# connect.net
KiCad netlist of a schematic drawn in Altium Designer
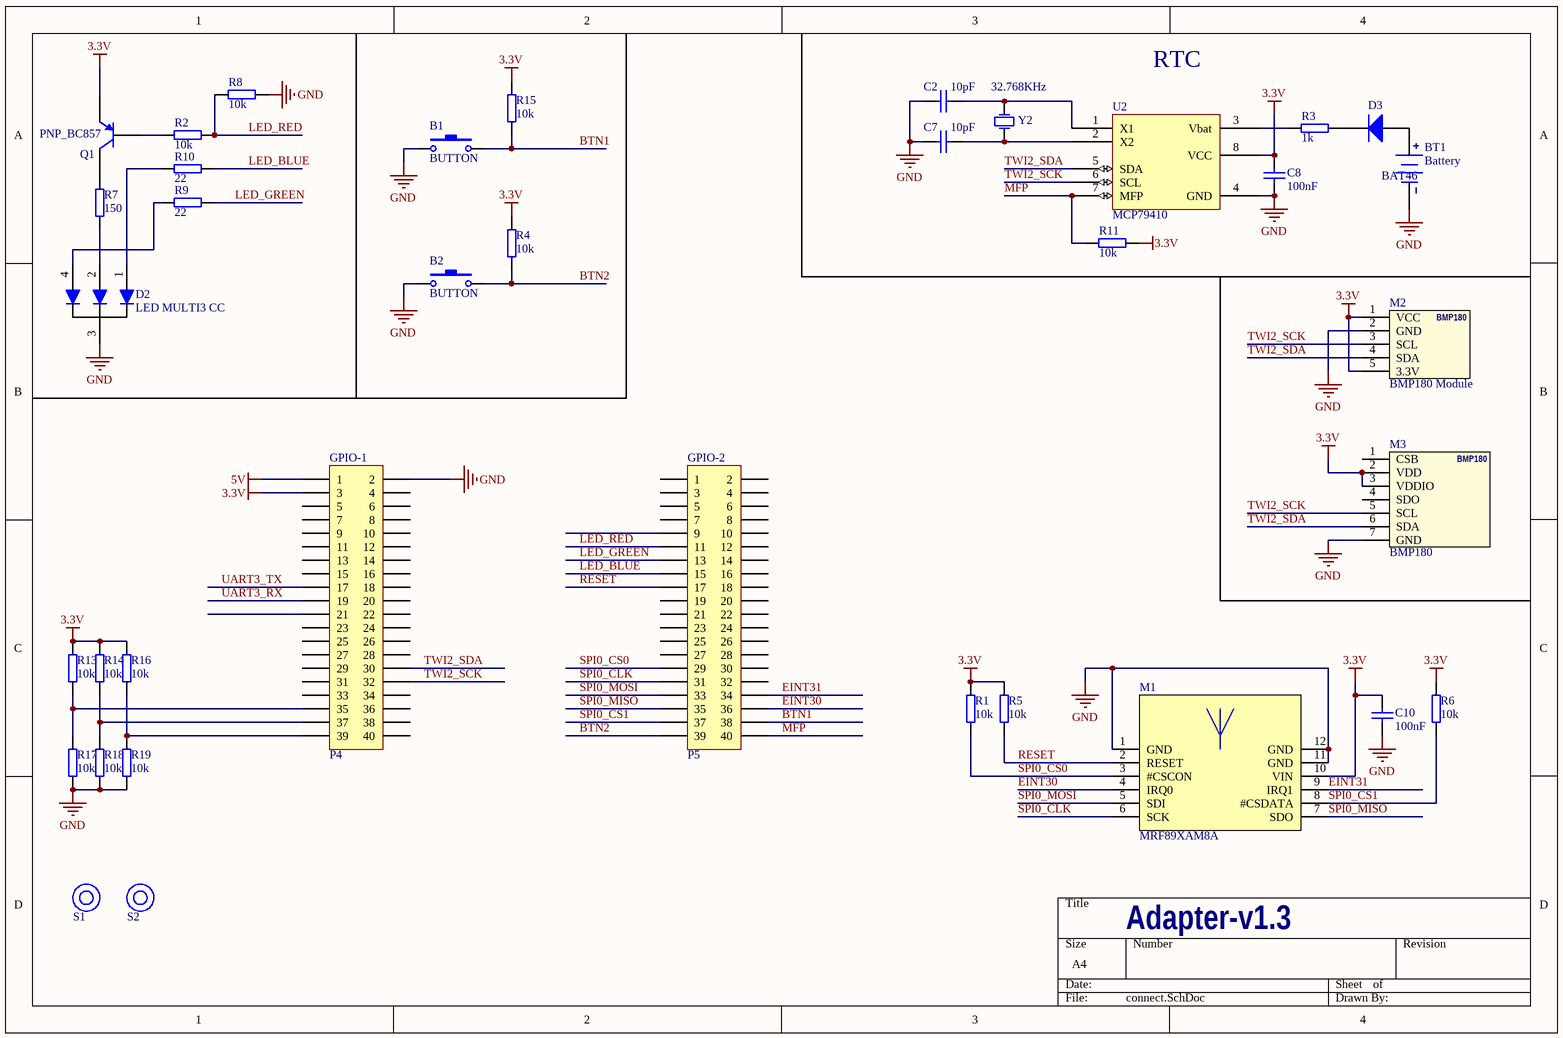
[diagram p0: connect.SchDoc]

(export (version "E")
  (design (tool "Eeschema 10.0.6"))
  (components
    (comp (ref "B1")
      (value "BUTTON")
      (footprint "SPST_BTN")
      (description "Switch Button KSS341G")
      (fields (field (name "PUBLISHER") "Altium Limited"))
      (libsource (lib "ANY Devices") (part "SW-PB_1"))
    )
    (comp (ref "B2")
      (value "BUTTON")
      (footprint "SPST_BTN")
      (description "Switch Button KSS341G")
      (fields (field (name "PUBLISHER") "Altium Limited"))
      (libsource (lib "ANY Devices") (part "SW-PB_1"))
    )
    (comp (ref "BT1")
      (value "Battery")
      (footprint "BATT1220-horizontal")
      (description "Multicell Battery")
      (fields (field (name "PUBLISHER") "Altium Limited"))
      (libsource (lib "ANY Devices") (part "Battery"))
    )
    (comp (ref "C2")
      (value "10pF")
      (footprint "C0805")
      (description "Capacitor")
      (fields (field (name "PUBLISHER") "Altium Limited"))
      (libsource (lib "ANY Devices") (part "Cap"))
    )
    (comp (ref "C7")
      (value "10pF")
      (footprint "C0805")
      (description "Capacitor")
      (fields (field (name "PUBLISHER") "Altium Limited"))
      (libsource (lib "ANY Devices") (part "Cap"))
    )
    (comp (ref "C8")
      (value "100nF")
      (footprint "C0805")
      (description "Capacitor")
      (fields (field (name "PUBLISHER") "Altium Limited"))
      (libsource (lib "ANY Devices") (part "Cap"))
    )
    (comp (ref "C10")
      (value "100nF")
      (footprint "C0805")
      (description "Capacitor")
      (fields (field (name "PUBLISHER") "Altium Limited"))
      (libsource (lib "ANY Devices") (part "Cap"))
    )
    (comp (ref "D2")
      (value "LED MULTI3 CC")
      (footprint "LED_MULTI - AXIAL")
      (description "COMMON CATHODE, HSMF-A211-A00J1 - LED, SMD, RED/YEL-GRN")
      (libsource (lib "ANY Devices") (part "LED MULTI3 CC"))
    )
    (comp (ref "D3")
      (value "BAT46")
      (footprint "SOD-323")
      (description "Default Diode")
      (fields (field (name "PUBLISHER") "Altium Limited"))
      (libsource (lib "ANY Devices") (part "Diode"))
    )
    (comp (ref "M1")
      (value "MRF89XAM8A")
      (footprint "MRF89XAM8A")
      (description "868 MHz Ultra-Low Power  Sub-GHz Transceiver Module")
      (libsource (lib "Modules") (part "MRF89XAM8A"))
    )
    (comp (ref "M2")
      (value "BMP180 Module")
      (footprint "BMP180_MODULE")
      (description "Digital Barometric Pressure Sensor Module")
      (libsource (lib "Modules") (part "BMP180_MODULE"))
    )
    (comp (ref "M3")
      (value "BMP180")
      (footprint "BMP180")
      (description "Digital pressure sensor")
      (libsource (lib "ANY Devices") (part "BMP180"))
    )
    (comp (ref "P4")
      (value "GPIO-1")
      (footprint "HDR127-20-F")
      (description "Header, 40-Pin, pitch 1.27mm")
      (fields (field (name "PUBLISHER") "Altium Limited"))
      (libsource (lib "ANY Connectors") (part "HDR127 20X2"))
    )
    (comp (ref "P5")
      (value "GPIO-2")
      (footprint "HDR127-20-F")
      (description "Header, 40-Pin, pitch 1.27mm")
      (fields (field (name "PUBLISHER") "Altium Limited"))
      (libsource (lib "ANY Connectors") (part "HDR127 20X2"))
    )
    (comp (ref "Q1")
      (value "PNP_BC857")
      (footprint "SOT23")
      (description "PNP Bipolar Transistor")
      (fields (field (name "PUBLISHER") "Altium Limited"))
      (libsource (lib "ANY Devices") (part "PNP_BC857"))
    )
    (comp (ref "R1")
      (value "10k")
      (footprint "R0805")
      (description "Resistor")
      (fields (field (name "PUBLISHER") "Altium Limited"))
      (libsource (lib "") (part "Res2_2"))
    )
    (comp (ref "R2")
      (value "10k")
      (footprint "R0805")
      (description "Resistor")
      (fields (field (name "PUBLISHER") "Altium Limited"))
      (libsource (lib "") (part "Res2_1"))
    )
    (comp (ref "R3")
      (value "1k")
      (footprint "R0805")
      (description "Resistor")
      (fields (field (name "PUBLISHER") "Altium Limited"))
      (libsource (lib "") (part "Res2_3"))
    )
    (comp (ref "R4")
      (value "10k")
      (footprint "R0805")
      (description "Resistor")
      (fields (field (name "PUBLISHER") "Altium Limited"))
      (libsource (lib "") (part "Res2_2"))
    )
    (comp (ref "R5")
      (value "10k")
      (footprint "R0805")
      (description "Resistor")
      (fields (field (name "PUBLISHER") "Altium Limited"))
      (libsource (lib "") (part "Res2_2"))
    )
    (comp (ref "R6")
      (value "10k")
      (footprint "R0805")
      (description "Resistor")
      (fields (field (name "PUBLISHER") "Altium Limited"))
      (libsource (lib "") (part "Res2_2"))
    )
    (comp (ref "R7")
      (value "150")
      (footprint "R0805")
      (description "Resistor")
      (fields (field (name "PUBLISHER") "Altium Limited"))
      (libsource (lib "ANY Devices") (part "Res2"))
    )
    (comp (ref "R8")
      (value "10k")
      (footprint "R0805")
      (description "Resistor")
      (fields (field (name "PUBLISHER") "Altium Limited"))
      (libsource (lib "") (part "Res2_1"))
    )
    (comp (ref "R9")
      (value "22")
      (footprint "R0805")
      (description "Resistor")
      (fields (field (name "PUBLISHER") "Altium Limited"))
      (libsource (lib "") (part "Res2_1"))
    )
    (comp (ref "R10")
      (value "22")
      (footprint "R0805")
      (description "Resistor")
      (fields (field (name "PUBLISHER") "Altium Limited"))
      (libsource (lib "") (part "Res2_3"))
    )
    (comp (ref "R11")
      (value "10k")
      (footprint "R0805")
      (description "Resistor")
      (fields (field (name "PUBLISHER") "Altium Limited"))
      (libsource (lib "") (part "Res2_1"))
    )
    (comp (ref "R13")
      (value "10k")
      (footprint "R0805")
      (description "Resistor")
      (fields (field (name "PUBLISHER") "Altium Limited"))
      (libsource (lib "ANY Devices") (part "Res2"))
    )
    (comp (ref "R14")
      (value "10k")
      (footprint "R0805")
      (description "Resistor")
      (fields (field (name "PUBLISHER") "Altium Limited"))
      (libsource (lib "ANY Devices") (part "Res2"))
    )
    (comp (ref "R15")
      (value "10k")
      (footprint "R0805")
      (description "Resistor")
      (fields (field (name "PUBLISHER") "Altium Limited"))
      (libsource (lib "") (part "Res2_2"))
    )
    (comp (ref "R16")
      (value "10k")
      (footprint "R0805")
      (description "Resistor")
      (fields (field (name "PUBLISHER") "Altium Limited"))
      (libsource (lib "ANY Devices") (part "Res2"))
    )
    (comp (ref "R17")
      (value "10k")
      (footprint "R0805")
      (description "Resistor")
      (fields (field (name "PUBLISHER") "Altium Limited"))
      (libsource (lib "ANY Devices") (part "Res2"))
    )
    (comp (ref "R18")
      (value "10k")
      (footprint "R0805")
      (description "Resistor")
      (fields (field (name "PUBLISHER") "Altium Limited"))
      (libsource (lib "ANY Devices") (part "Res2"))
    )
    (comp (ref "R19")
      (value "10k")
      (footprint "R0805")
      (description "Resistor")
      (fields (field (name "PUBLISHER") "Altium Limited"))
      (libsource (lib "ANY Devices") (part "Res2"))
    )
    (comp (ref "S1") (value "TARGET") (footprint "TARGET") (libsource (lib "ANY Devices") (part "TARGET")))
    (comp (ref "S2") (value "TARGET") (footprint "TARGET") (libsource (lib "ANY Devices") (part "TARGET")))
    (comp (ref "U2")
      (value "MCP79410")
      (footprint "SO8_M")
      (description "Microchip i2c RTC real time clock")
      (libsource (lib "ANYlib") (part "MCP79410"))
    )
    (comp (ref "Y2")
      (value "32.768KHz")
      (footprint "R38")
      (description "Crystal Oscillator")
      (fields (field (name "PUBLISHER") "Altium Limited"))
      (libsource (lib "ANY Devices") (part "XTAL"))
    )
  )
  (nets
    (net (code "1") (name "/BTN1") (class "Default")
      (node (ref "B1") (pin "2") (pinfunction "2_2") (pintype "passive"))
      (node (ref "P5") (pin "38") (pinfunction "38_38") (pintype "passive"))
      (node (ref "R15") (pin "1") (pinfunction "1_1") (pintype "passive"))
    )
    (net (code "2") (name "/BTN2") (class "Default")
      (node (ref "B2") (pin "2") (pinfunction "2_2") (pintype "passive"))
      (node (ref "P5") (pin "39") (pinfunction "39_39") (pintype "passive"))
      (node (ref "R4") (pin "1") (pinfunction "1_1") (pintype "passive"))
    )
    (net (code "3") (name "/EINT30") (class "Default")
      (node (ref "M1") (pin "4") (pinfunction "IRQ0_4") (pintype "passive"))
      (node (ref "P5") (pin "36") (pinfunction "36_36") (pintype "passive"))
    )
    (net (code "4") (name "/EINT31") (class "Default")
      (node (ref "M1") (pin "9") (pinfunction "IRQ1_9") (pintype "passive"))
      (node (ref "P5") (pin "34") (pinfunction "34_34") (pintype "passive"))
    )
    (net (code "5") (name "/LED_BLUE") (class "Default")
      (node (ref "P5") (pin "15") (pinfunction "15_15") (pintype "passive"))
      (node (ref "R10") (pin "2") (pinfunction "2_2") (pintype "passive"))
    )
    (net (code "6") (name "/LED_GREEN") (class "Default")
      (node (ref "P5") (pin "13") (pinfunction "13_13") (pintype "passive"))
      (node (ref "R9") (pin "1") (pinfunction "1_1") (pintype "passive"))
    )
    (net (code "7") (name "/LED_RED") (class "Default")
      (node (ref "P5") (pin "11") (pinfunction "11_11") (pintype "passive"))
      (node (ref "R2") (pin "1") (pinfunction "1_1") (pintype "passive"))
      (node (ref "R8") (pin "2") (pinfunction "2_2") (pintype "passive"))
    )
    (net (code "8") (name "/MFP") (class "Default")
      (node (ref "P5") (pin "40") (pinfunction "40_40") (pintype "passive"))
      (node (ref "R11") (pin "2") (pinfunction "2_2") (pintype "passive"))
      (node (ref "U2") (pin "7") (pinfunction "MFP_7") (pintype "bidirectional"))
    )
    (net (code "9") (name "/RESET") (class "Default")
      (node (ref "M1") (pin "2") (pinfunction "RESET_2") (pintype "passive"))
      (node (ref "P5") (pin "17") (pinfunction "17_17") (pintype "passive"))
      (node (ref "R5") (pin "1") (pinfunction "1_1") (pintype "passive"))
    )
    (net (code "10") (name "/SPI0_CLK") (class "Default")
      (node (ref "M1") (pin "6") (pinfunction "SCK_6") (pintype "passive"))
      (node (ref "P5") (pin "31") (pinfunction "31_31") (pintype "passive"))
    )
    (net (code "11") (name "/SPI0_CS0") (class "Default")
      (node (ref "M1") (pin "3") (pinfunction "#CSCON_3") (pintype "passive"))
      (node (ref "P5") (pin "29") (pinfunction "29_29") (pintype "passive"))
      (node (ref "R1") (pin "1") (pinfunction "1_1") (pintype "passive"))
    )
    (net (code "12") (name "/SPI0_CS1") (class "Default")
      (node (ref "M1") (pin "8") (pinfunction "#CSDATA_8") (pintype "passive"))
      (node (ref "P5") (pin "37") (pinfunction "37_37") (pintype "passive"))
      (node (ref "R6") (pin "1") (pinfunction "1_1") (pintype "passive"))
    )
    (net (code "13") (name "/SPI0_MISO") (class "Default")
      (node (ref "M1") (pin "7") (pinfunction "SDO_7") (pintype "passive"))
      (node (ref "P5") (pin "35") (pinfunction "35_35") (pintype "passive"))
    )
    (net (code "14") (name "/SPI0_MOSI") (class "Default")
      (node (ref "M1") (pin "5") (pinfunction "SDI_5") (pintype "passive"))
      (node (ref "P5") (pin "33") (pinfunction "33_33") (pintype "passive"))
    )
    (net (code "15") (name "/TWI2_SCK") (class "Default")
      (node (ref "M2") (pin "3") (pinfunction "SCL_3") (pintype "passive"))
      (node (ref "M3") (pin "5") (pinfunction "SCL_5") (pintype "passive"))
      (node (ref "P4") (pin "32") (pinfunction "32_32") (pintype "passive"))
      (node (ref "U2") (pin "6") (pinfunction "SCL_6") (pintype "bidirectional"))
    )
    (net (code "16") (name "/TWI2_SDA") (class "Default")
      (node (ref "M2") (pin "4") (pinfunction "SDA_4") (pintype "passive"))
      (node (ref "M3") (pin "6") (pinfunction "SDA_6") (pintype "passive"))
      (node (ref "P4") (pin "30") (pinfunction "30_30") (pintype "passive"))
      (node (ref "U2") (pin "5") (pinfunction "SDA_5") (pintype "bidirectional"))
    )
    (net (code "17") (name "/UART3_RX") (class "Default")
      (node (ref "P4") (pin "19") (pinfunction "19_19") (pintype "passive"))
    )
    (net (code "18") (name "/UART3_TX") (class "Default")
      (node (ref "P4") (pin "17") (pinfunction "17_17") (pintype "passive"))
    )
    (net (code "19") (name "3.3V") (class "Default")
      (node (ref "C10") (pin "2") (pinfunction "2_2") (pintype "passive"))
      (node (ref "C8") (pin "2") (pinfunction "2_2") (pintype "passive"))
      (node (ref "M1") (pin "10") (pinfunction "VIN_10") (pintype "passive"))
      (node (ref "M2") (pin "1") (pinfunction "VCC_1") (pintype "passive"))
      (node (ref "M2") (pin "5") (pinfunction "3.3V_5") (pintype "passive"))
      (node (ref "M3") (pin "2") (pinfunction "VDD_2") (pintype "passive"))
      (node (ref "M3") (pin "3") (pinfunction "VDDIO_3") (pintype "passive"))
      (node (ref "P4") (pin "3") (pinfunction "3_3") (pintype "passive"))
      (node (ref "Q1") (pin "2") (pinfunction "E_2") (pintype "passive"))
      (node (ref "R1") (pin "2") (pinfunction "2_2") (pintype "passive"))
      (node (ref "R11") (pin "1") (pinfunction "1_1") (pintype "passive"))
      (node (ref "R13") (pin "1") (pinfunction "1_1") (pintype "passive"))
      (node (ref "R14") (pin "1") (pinfunction "1_1") (pintype "passive"))
      (node (ref "R15") (pin "2") (pinfunction "2_2") (pintype "passive"))
      (node (ref "R16") (pin "1") (pinfunction "1_1") (pintype "passive"))
      (node (ref "R4") (pin "2") (pinfunction "2_2") (pintype "passive"))
      (node (ref "R5") (pin "2") (pinfunction "2_2") (pintype "passive"))
      (node (ref "R6") (pin "2") (pinfunction "2_2") (pintype "passive"))
      (node (ref "U2") (pin "8") (pinfunction "VCC_8") (pintype "power_in"))
    )
    (net (code "20") (name "5V") (class "Default")
      (node (ref "P4") (pin "1") (pinfunction "1_1") (pintype "passive"))
    )
    (net (code "21") (name "GND") (class "Default")
      (node (ref "B1") (pin "1") (pinfunction "1_1") (pintype "passive"))
      (node (ref "B2") (pin "1") (pinfunction "1_1") (pintype "passive"))
      (node (ref "BT1") (pin "2") (pinfunction "-_2") (pintype "passive"))
      (node (ref "C10") (pin "1") (pinfunction "1_1") (pintype "passive"))
      (node (ref "C2") (pin "1") (pinfunction "1_1") (pintype "passive"))
      (node (ref "C7") (pin "1") (pinfunction "1_1") (pintype "passive"))
      (node (ref "C8") (pin "1") (pinfunction "1_1") (pintype "passive"))
      (node (ref "D2") (pin "3") (pinfunction "C_3") (pintype "passive"))
      (node (ref "M1") (pin "1") (pinfunction "GND_1") (pintype "passive"))
      (node (ref "M1") (pin "11") (pinfunction "GND_11") (pintype "passive"))
      (node (ref "M1") (pin "12") (pinfunction "GND_12") (pintype "passive"))
      (node (ref "M2") (pin "2") (pinfunction "GND_2") (pintype "passive"))
      (node (ref "M3") (pin "7") (pinfunction "GND_7") (pintype "passive"))
      (node (ref "P4") (pin "2") (pinfunction "2_2") (pintype "passive"))
      (node (ref "R17") (pin "2") (pinfunction "2_2") (pintype "passive"))
      (node (ref "R18") (pin "2") (pinfunction "2_2") (pintype "passive"))
      (node (ref "R19") (pin "2") (pinfunction "2_2") (pintype "passive"))
      (node (ref "R8") (pin "1") (pinfunction "1_1") (pintype "passive"))
      (node (ref "U2") (pin "4") (pinfunction "GND_4") (pintype "power_in"))
    )
    (net (code "22") (name "Net-(BT1-+)") (class "Default")
      (node (ref "BT1") (pin "1") (pinfunction "+_1") (pintype "passive"))
      (node (ref "D3") (pin "1") (pinfunction "A_1") (pintype "passive"))
    )
    (net (code "23") (name "Net-(D2-A)") (class "Default")
      (node (ref "D2") (pin "2") (pinfunction "A_2") (pintype "passive"))
      (node (ref "R7") (pin "2") (pinfunction "2_2") (pintype "passive"))
    )
    (net (code "24") (name "Net-(D2-C-Pad1)") (class "Default")
      (node (ref "D2") (pin "1") (pinfunction "C_1") (pintype "passive"))
      (node (ref "R10") (pin "1") (pinfunction "1_1") (pintype "passive"))
    )
    (net (code "25") (name "Net-(D2-C-Pad4)") (class "Default")
      (node (ref "D2") (pin "4") (pinfunction "C_4") (pintype "passive"))
      (node (ref "R9") (pin "2") (pinfunction "2_2") (pintype "passive"))
    )
    (net (code "26") (name "Net-(D3-K)") (class "Default")
      (node (ref "D3") (pin "2") (pinfunction "K_2") (pintype "passive"))
      (node (ref "R3") (pin "2") (pinfunction "2_2") (pintype "passive"))
    )
    (net (code "27") (name "Net-(P4-Pad35)") (class "Default")
      (node (ref "P4") (pin "35") (pinfunction "35_35") (pintype "passive"))
      (node (ref "R13") (pin "2") (pinfunction "2_2") (pintype "passive"))
      (node (ref "R17") (pin "1") (pinfunction "1_1") (pintype "passive"))
    )
    (net (code "28") (name "Net-(P4-Pad37)") (class "Default")
      (node (ref "P4") (pin "37") (pinfunction "37_37") (pintype "passive"))
      (node (ref "R14") (pin "2") (pinfunction "2_2") (pintype "passive"))
      (node (ref "R18") (pin "1") (pinfunction "1_1") (pintype "passive"))
    )
    (net (code "29") (name "Net-(P4-Pad39)") (class "Default")
      (node (ref "P4") (pin "39") (pinfunction "39_39") (pintype "passive"))
      (node (ref "R16") (pin "2") (pinfunction "2_2") (pintype "passive"))
      (node (ref "R19") (pin "1") (pinfunction "1_1") (pintype "passive"))
    )
    (net (code "30") (name "Net-(Q1-B)") (class "Default")
      (node (ref "Q1") (pin "1") (pinfunction "B_1") (pintype "passive"))
      (node (ref "R2") (pin "2") (pinfunction "2_2") (pintype "passive"))
    )
    (net (code "31") (name "Net-(Q1-C)") (class "Default")
      (node (ref "Q1") (pin "3") (pinfunction "C_3") (pintype "passive"))
      (node (ref "R7") (pin "1") (pinfunction "1_1") (pintype "passive"))
    )
    (net (code "32") (name "Net-(U2-Vbat)") (class "Default")
      (node (ref "R3") (pin "1") (pinfunction "1_1") (pintype "passive"))
      (node (ref "U2") (pin "3") (pinfunction "Vbat_3") (pintype "power_in"))
    )
    (net (code "33") (name "Net-(U2-X1)") (class "Default")
      (node (ref "C2") (pin "2") (pinfunction "2_2") (pintype "passive"))
      (node (ref "U2") (pin "1") (pinfunction "X1_1") (pintype "passive"))
      (node (ref "Y2") (pin "2") (pinfunction "OSC2_2") (pintype "passive"))
    )
    (net (code "34") (name "Net-(U2-X2)") (class "Default")
      (node (ref "C7") (pin "2") (pinfunction "2_2") (pintype "passive"))
      (node (ref "U2") (pin "2") (pinfunction "X2_2") (pintype "passive"))
      (node (ref "Y2") (pin "1") (pinfunction "OSC1_1") (pintype "passive"))
    )
    (net (code "35") (name "unconnected-(M3-CSB-Pad1)") (class "Default")
      (node (ref "M3") (pin "1") (pinfunction "CSB_1") (pintype "passive"))
    )
    (net (code "36") (name "unconnected-(M3-SDO-Pad4)") (class "Default")
      (node (ref "M3") (pin "4") (pinfunction "SDO_4") (pintype "passive"))
    )
    (net (code "37") (name "unconnected-(P4-Pad4)") (class "Default")
      (node (ref "P4") (pin "4") (pinfunction "4_4") (pintype "passive"))
    )
    (net (code "38") (name "unconnected-(P4-Pad5)") (class "Default")
      (node (ref "P4") (pin "5") (pinfunction "5_5") (pintype "passive"))
    )
    (net (code "39") (name "unconnected-(P4-Pad6)") (class "Default")
      (node (ref "P4") (pin "6") (pinfunction "6_6") (pintype "passive"))
    )
    (net (code "40") (name "unconnected-(P4-Pad7)") (class "Default")
      (node (ref "P4") (pin "7") (pinfunction "7_7") (pintype "passive"))
    )
    (net (code "41") (name "unconnected-(P4-Pad8)") (class "Default")
      (node (ref "P4") (pin "8") (pinfunction "8_8") (pintype "passive"))
    )
    (net (code "42") (name "unconnected-(P4-Pad9)") (class "Default")
      (node (ref "P4") (pin "9") (pinfunction "9_9") (pintype "passive"))
    )
    (net (code "43") (name "unconnected-(P4-Pad10)") (class "Default")
      (node (ref "P4") (pin "10") (pinfunction "10_10") (pintype "passive"))
    )
    (net (code "44") (name "unconnected-(P4-Pad11)") (class "Default")
      (node (ref "P4") (pin "11") (pinfunction "11_11") (pintype "passive"))
    )
    (net (code "45") (name "unconnected-(P4-Pad12)") (class "Default")
      (node (ref "P4") (pin "12") (pinfunction "12_12") (pintype "passive"))
    )
    (net (code "46") (name "unconnected-(P4-Pad13)") (class "Default")
      (node (ref "P4") (pin "13") (pinfunction "13_13") (pintype "passive"))
    )
    (net (code "47") (name "unconnected-(P4-Pad14)") (class "Default")
      (node (ref "P4") (pin "14") (pinfunction "14_14") (pintype "passive"))
    )
    (net (code "48") (name "unconnected-(P4-Pad15)") (class "Default")
      (node (ref "P4") (pin "15") (pinfunction "15_15") (pintype "passive"))
    )
    (net (code "49") (name "unconnected-(P4-Pad16)") (class "Default")
      (node (ref "P4") (pin "16") (pinfunction "16_16") (pintype "passive"))
    )
    (net (code "50") (name "unconnected-(P4-Pad18)") (class "Default")
      (node (ref "P4") (pin "18") (pinfunction "18_18") (pintype "passive"))
    )
    (net (code "51") (name "unconnected-(P4-Pad20)") (class "Default")
      (node (ref "P4") (pin "20") (pinfunction "20_20") (pintype "passive"))
    )
    (net (code "52") (name "unconnected-(P4-Pad21)") (class "Default")
      (node (ref "P4") (pin "21") (pinfunction "21_21") (pintype "passive"))
    )
    (net (code "53") (name "unconnected-(P4-Pad22)") (class "Default")
      (node (ref "P4") (pin "22") (pinfunction "22_22") (pintype "passive"))
    )
    (net (code "54") (name "unconnected-(P4-Pad23)") (class "Default")
      (node (ref "P4") (pin "23") (pinfunction "23_23") (pintype "passive"))
    )
    (net (code "55") (name "unconnected-(P4-Pad24)") (class "Default")
      (node (ref "P4") (pin "24") (pinfunction "24_24") (pintype "passive"))
    )
    (net (code "56") (name "unconnected-(P4-Pad25)") (class "Default")
      (node (ref "P4") (pin "25") (pinfunction "25_25") (pintype "passive"))
    )
    (net (code "57") (name "unconnected-(P4-Pad26)") (class "Default")
      (node (ref "P4") (pin "26") (pinfunction "26_26") (pintype "passive"))
    )
    (net (code "58") (name "unconnected-(P4-Pad27)") (class "Default")
      (node (ref "P4") (pin "27") (pinfunction "27_27") (pintype "passive"))
    )
    (net (code "59") (name "unconnected-(P4-Pad28)") (class "Default")
      (node (ref "P4") (pin "28") (pinfunction "28_28") (pintype "passive"))
    )
    (net (code "60") (name "unconnected-(P4-Pad29)") (class "Default")
      (node (ref "P4") (pin "29") (pinfunction "29_29") (pintype "passive"))
    )
    (net (code "61") (name "unconnected-(P4-Pad31)") (class "Default")
      (node (ref "P4") (pin "31") (pinfunction "31_31") (pintype "passive"))
    )
    (net (code "62") (name "unconnected-(P4-Pad33)") (class "Default")
      (node (ref "P4") (pin "33") (pinfunction "33_33") (pintype "passive"))
    )
    (net (code "63") (name "unconnected-(P4-Pad34)") (class "Default")
      (node (ref "P4") (pin "34") (pinfunction "34_34") (pintype "passive"))
    )
    (net (code "64") (name "unconnected-(P4-Pad36)") (class "Default")
      (node (ref "P4") (pin "36") (pinfunction "36_36") (pintype "passive"))
    )
    (net (code "65") (name "unconnected-(P4-Pad38)") (class "Default")
      (node (ref "P4") (pin "38") (pinfunction "38_38") (pintype "passive"))
    )
    (net (code "66") (name "unconnected-(P4-Pad40)") (class "Default")
      (node (ref "P4") (pin "40") (pinfunction "40_40") (pintype "passive"))
    )
    (net (code "67") (name "unconnected-(P5-Pad1)") (class "Default")
      (node (ref "P5") (pin "1") (pinfunction "1_1") (pintype "passive"))
    )
    (net (code "68") (name "unconnected-(P5-Pad2)") (class "Default")
      (node (ref "P5") (pin "2") (pinfunction "2_2") (pintype "passive"))
    )
    (net (code "69") (name "unconnected-(P5-Pad3)") (class "Default")
      (node (ref "P5") (pin "3") (pinfunction "3_3") (pintype "passive"))
    )
    (net (code "70") (name "unconnected-(P5-Pad4)") (class "Default")
      (node (ref "P5") (pin "4") (pinfunction "4_4") (pintype "passive"))
    )
    (net (code "71") (name "unconnected-(P5-Pad5)") (class "Default")
      (node (ref "P5") (pin "5") (pinfunction "5_5") (pintype "passive"))
    )
    (net (code "72") (name "unconnected-(P5-Pad6)") (class "Default")
      (node (ref "P5") (pin "6") (pinfunction "6_6") (pintype "passive"))
    )
    (net (code "73") (name "unconnected-(P5-Pad7)") (class "Default")
      (node (ref "P5") (pin "7") (pinfunction "7_7") (pintype "passive"))
    )
    (net (code "74") (name "unconnected-(P5-Pad8)") (class "Default")
      (node (ref "P5") (pin "8") (pinfunction "8_8") (pintype "passive"))
    )
    (net (code "75") (name "unconnected-(P5-Pad9)") (class "Default")
      (node (ref "P5") (pin "9") (pinfunction "9_9") (pintype "passive"))
    )
    (net (code "76") (name "unconnected-(P5-Pad10)") (class "Default")
      (node (ref "P5") (pin "10") (pinfunction "10_10") (pintype "passive"))
    )
    (net (code "77") (name "unconnected-(P5-Pad12)") (class "Default")
      (node (ref "P5") (pin "12") (pinfunction "12_12") (pintype "passive"))
    )
    (net (code "78") (name "unconnected-(P5-Pad14)") (class "Default")
      (node (ref "P5") (pin "14") (pinfunction "14_14") (pintype "passive"))
    )
    (net (code "79") (name "unconnected-(P5-Pad16)") (class "Default")
      (node (ref "P5") (pin "16") (pinfunction "16_16") (pintype "passive"))
    )
    (net (code "80") (name "unconnected-(P5-Pad18)") (class "Default")
      (node (ref "P5") (pin "18") (pinfunction "18_18") (pintype "passive"))
    )
    (net (code "81") (name "unconnected-(P5-Pad19)") (class "Default")
      (node (ref "P5") (pin "19") (pinfunction "19_19") (pintype "passive"))
    )
    (net (code "82") (name "unconnected-(P5-Pad20)") (class "Default")
      (node (ref "P5") (pin "20") (pinfunction "20_20") (pintype "passive"))
    )
    (net (code "83") (name "unconnected-(P5-Pad21)") (class "Default")
      (node (ref "P5") (pin "21") (pinfunction "21_21") (pintype "passive"))
    )
    (net (code "84") (name "unconnected-(P5-Pad22)") (class "Default")
      (node (ref "P5") (pin "22") (pinfunction "22_22") (pintype "passive"))
    )
    (net (code "85") (name "unconnected-(P5-Pad23)") (class "Default")
      (node (ref "P5") (pin "23") (pinfunction "23_23") (pintype "passive"))
    )
    (net (code "86") (name "unconnected-(P5-Pad24)") (class "Default")
      (node (ref "P5") (pin "24") (pinfunction "24_24") (pintype "passive"))
    )
    (net (code "87") (name "unconnected-(P5-Pad25)") (class "Default")
      (node (ref "P5") (pin "25") (pinfunction "25_25") (pintype "passive"))
    )
    (net (code "88") (name "unconnected-(P5-Pad26)") (class "Default")
      (node (ref "P5") (pin "26") (pinfunction "26_26") (pintype "passive"))
    )
    (net (code "89") (name "unconnected-(P5-Pad27)") (class "Default")
      (node (ref "P5") (pin "27") (pinfunction "27_27") (pintype "passive"))
    )
    (net (code "90") (name "unconnected-(P5-Pad28)") (class "Default")
      (node (ref "P5") (pin "28") (pinfunction "28_28") (pintype "passive"))
    )
    (net (code "91") (name "unconnected-(P5-Pad30)") (class "Default")
      (node (ref "P5") (pin "30") (pinfunction "30_30") (pintype "passive"))
    )
    (net (code "92") (name "unconnected-(P5-Pad32)") (class "Default")
      (node (ref "P5") (pin "32") (pinfunction "32_32") (pintype "passive"))
    )
  )
)
